# 10_USB.net
KiCad netlist of a schematic drawn in Altium Designer
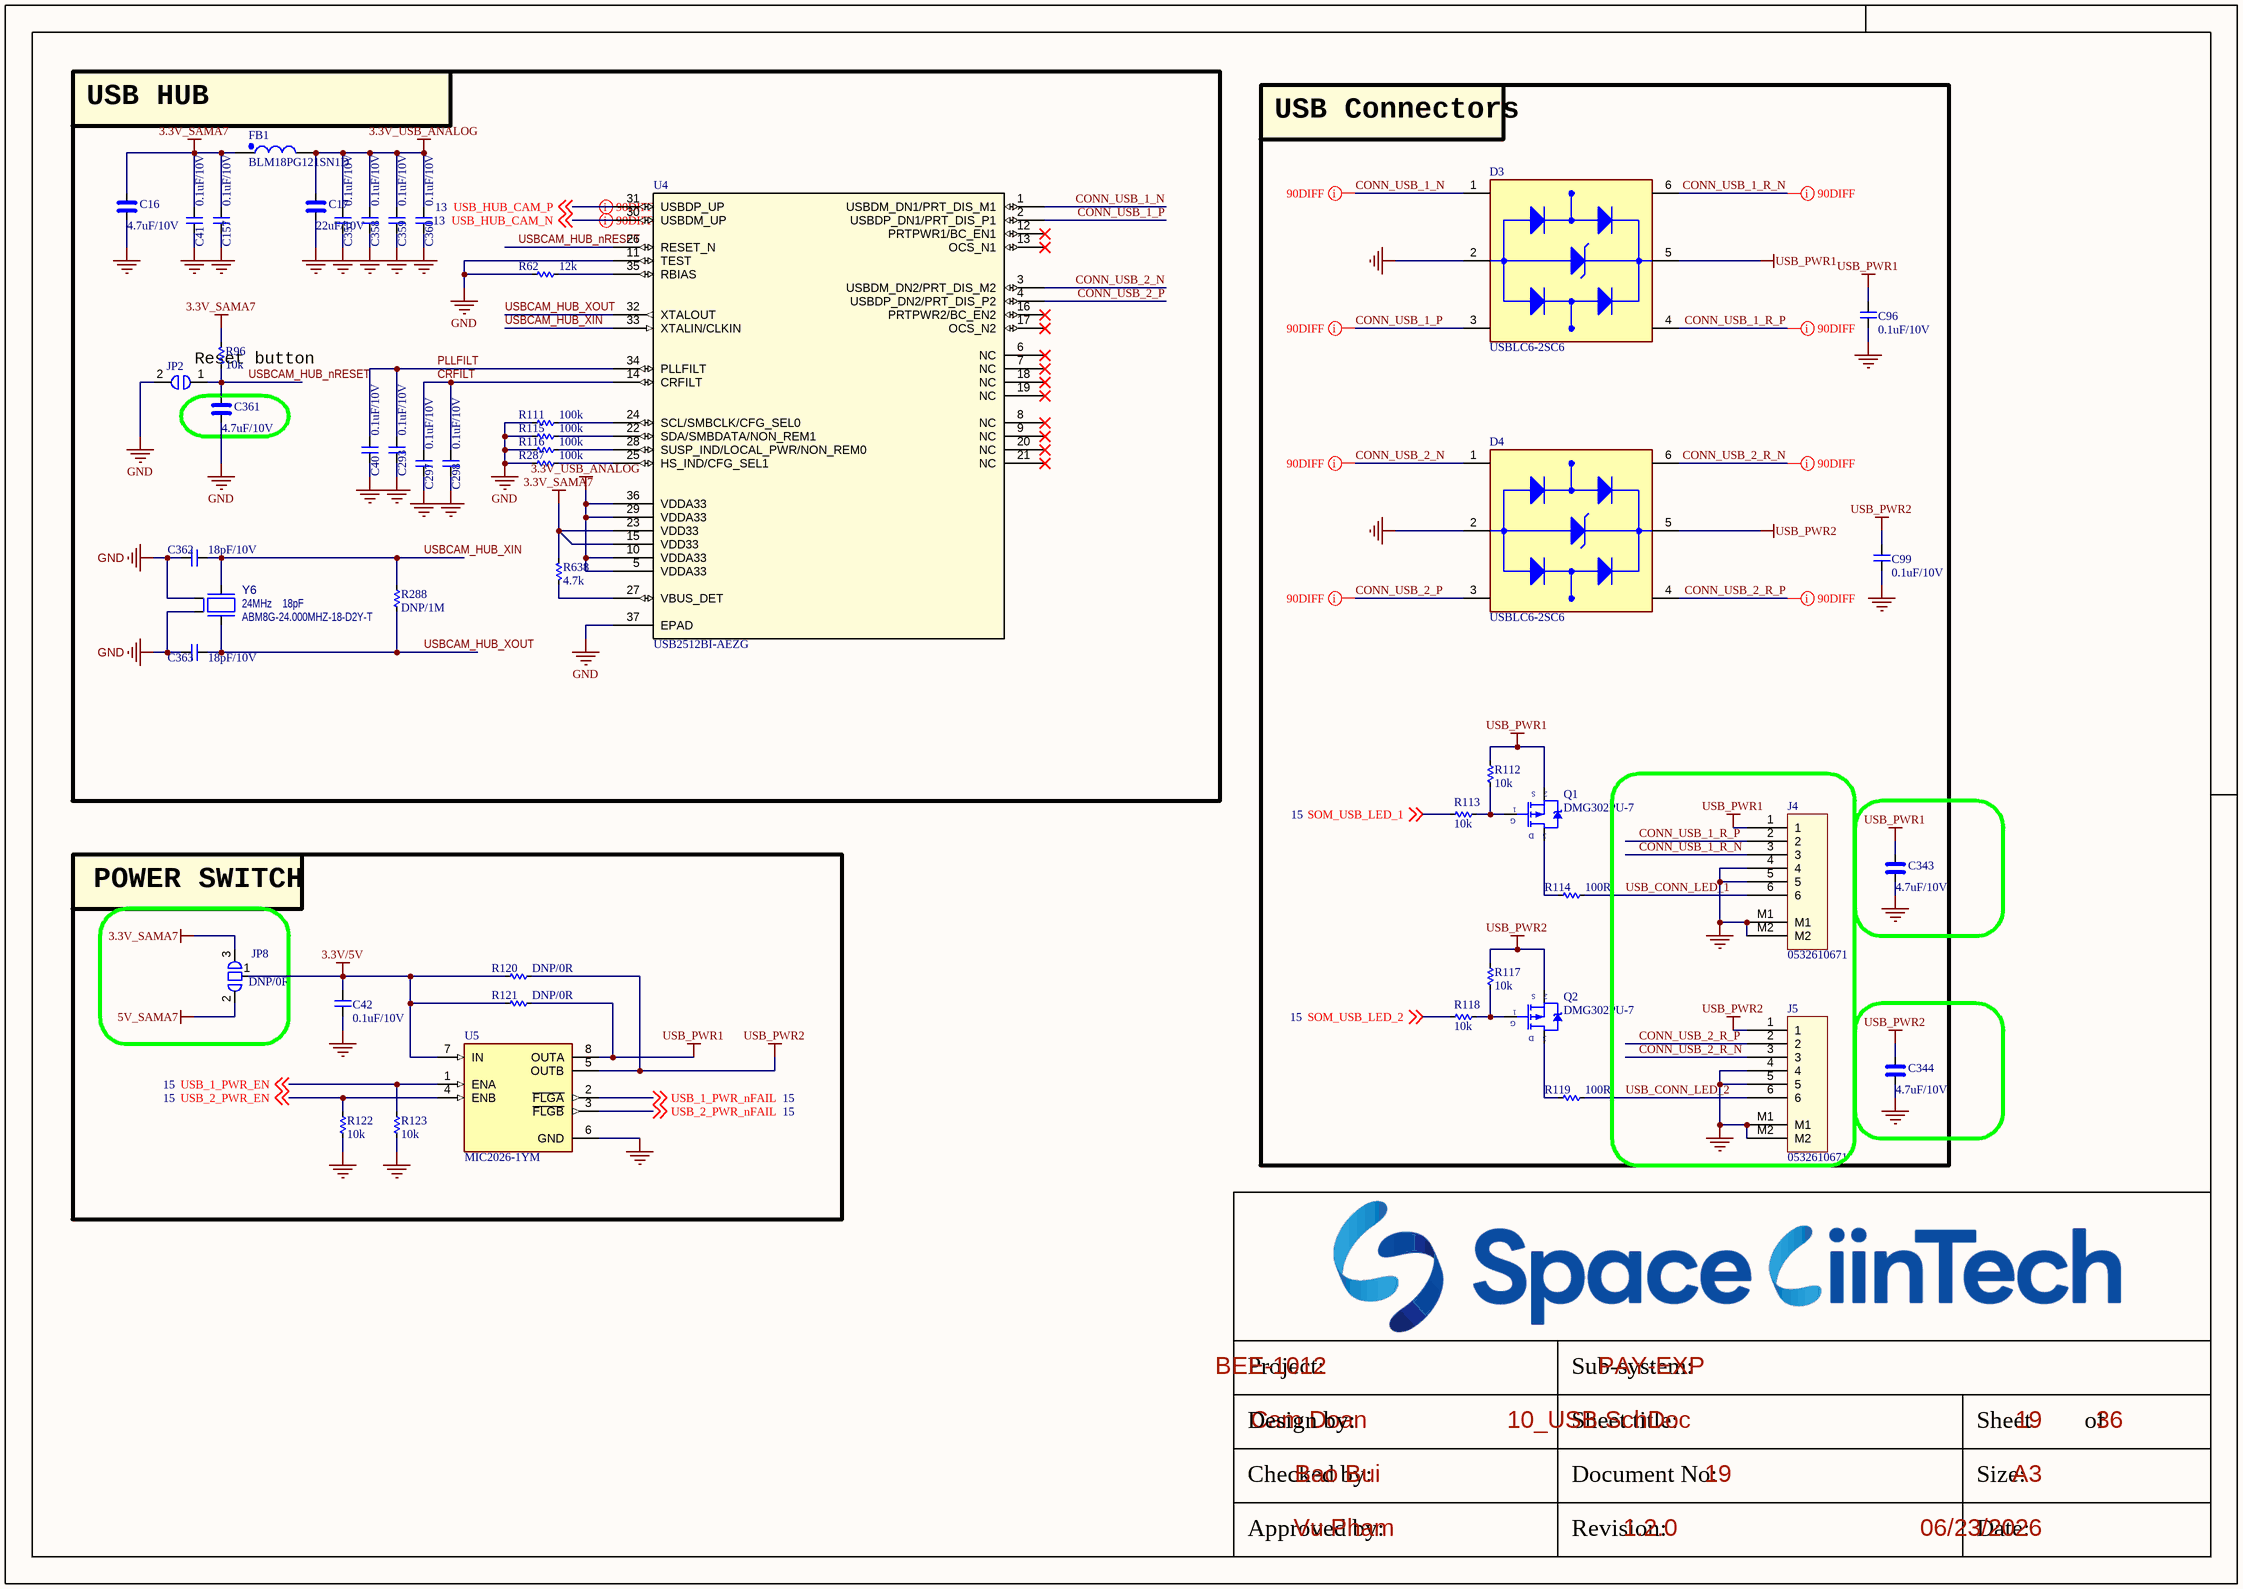
[diagram p0: 10_USB.SchDoc]

(export (version "E")
  (design (tool "Eeschema 10.0.6"))
  (components
    (comp (ref "C16")
      (value "4.7uF/10V")
      (footprint "CAP_C_1608X80")
      (description "CAP CHIP High Value")
      (libsource (lib "LABLIB") (part "_CAP_C_High_2"))
    )
    (comp (ref "C17")
      (value "22uF/10V")
      (footprint "CAP_C_1608X80")
      (description "CAP CHIP High Value")
      (libsource (lib "LABLIB") (part "_CAP_C_High_2"))
    )
    (comp (ref "C40")
      (value "0.1uF/10V")
      (footprint "CAP_C_1005X60")
      (description "CAP CHIP")
      (libsource (lib "LABLIB") (part "_CAP_C_2"))
    )
    (comp (ref "C41")
      (value "0.1uF/10V")
      (footprint "CAP_C_1005X60")
      (description "CAP CHIP")
      (libsource (lib "LABLIB") (part "_CAP_C_2"))
    )
    (comp (ref "C42")
      (value "0.1uF/10V")
      (footprint "CAP_C_1005X60")
      (description "CAP")
      (libsource (lib "LABLIB") (part "_CAP_C_2"))
    )
    (comp (ref "C96")
      (value "0.1uF/10V")
      (footprint "CAP_C_1005X60")
      (description "CAP")
      (libsource (lib "LABLIB") (part "_CAP_C_2"))
    )
    (comp (ref "C99")
      (value "0.1uF/10V")
      (footprint "CAP_C_1005X60")
      (description "CAP")
      (libsource (lib "LABLIB") (part "_CAP_C_2"))
    )
    (comp (ref "C157")
      (value "0.1uF/10V")
      (footprint "CAP_C_1005X60")
      (description "CAP CHIP")
      (libsource (lib "LABLIB") (part "_CAP_C_2"))
    )
    (comp (ref "C293")
      (value "0.1uF/10V")
      (footprint "CAP_C_1005X60")
      (description "CAP CHIP")
      (libsource (lib "LABLIB") (part "_CAP_C_2"))
    )
    (comp (ref "C297")
      (value "0.1uF/10V")
      (footprint "CAP_C_1005X60")
      (description "CAP CHIP")
      (libsource (lib "LABLIB") (part "_CAP_C_2"))
    )
    (comp (ref "C298")
      (value "0.1uF/10V")
      (footprint "CAP_C_1005X60")
      (description "CAP CHIP")
      (libsource (lib "LABLIB") (part "_CAP_C_2"))
    )
    (comp (ref "C343")
      (value "4.7uF/10V")
      (footprint "CAP_C_1608X80")
      (description "CAP CHIP High Value")
      (libsource (lib "LABLIB") (part "_CAP_C_High_2"))
    )
    (comp (ref "C344")
      (value "4.7uF/10V")
      (footprint "CAP_C_1608X80")
      (description "CAP CHIP High Value")
      (libsource (lib "LABLIB") (part "_CAP_C_High_2"))
    )
    (comp (ref "C357")
      (value "0.1uF/10V")
      (footprint "CAP_C_1005X60")
      (description "CAP CHIP")
      (libsource (lib "LABLIB") (part "_CAP_C_2"))
    )
    (comp (ref "C358")
      (value "0.1uF/10V")
      (footprint "CAP_C_1005X60")
      (description "CAP CHIP")
      (libsource (lib "LABLIB") (part "_CAP_C_2"))
    )
    (comp (ref "C359")
      (value "0.1uF/10V")
      (footprint "CAP_C_1005X60")
      (description "CAP CHIP")
      (libsource (lib "LABLIB") (part "_CAP_C_2"))
    )
    (comp (ref "C360")
      (value "0.1uF/10V")
      (footprint "CAP_C_1005X60")
      (description "CAP CHIP")
      (libsource (lib "LABLIB") (part "_CAP_C_2"))
    )
    (comp (ref "C361")
      (value "4.7uF/10V")
      (footprint "CAP_C_1608X80")
      (description "CAP CHIP High Value")
      (libsource (lib "LABLIB") (part "_CAP_C_High_2"))
    )
    (comp (ref "C362")
      (value "18pF/10V")
      (footprint "CAP_C_1005X60")
      (description "CAP CHIP")
      (libsource (lib "LABLIB") (part "_CAP_C_2"))
    )
    (comp (ref "C363")
      (value "18pF/10V")
      (footprint "CAP_C_1005X60")
      (description "CAP CHIP")
      (libsource (lib "LABLIB") (part "_CAP_C_2"))
    )
    (comp (ref "D3")
      (value "USBLC6-2SC6")
      (footprint "SOT95P280X145-6N")
      (description "17V Clamp 5A (8/20Âµs) Ipp Tvs Diode Surface Mount SOT-23-6")
      (fields (field (name "MF") "STMicroelectronics"))
      (libsource (lib "USBLC6-2SC6") (part "USBLC6-2SC6"))
    )
    (comp (ref "D4")
      (value "USBLC6-2SC6")
      (footprint "SOT95P280X145-6N")
      (description "17V Clamp 5A (8/20Âµs) Ipp Tvs Diode Surface Mount SOT-23-6")
      (fields (field (name "MF") "STMicroelectronics"))
      (libsource (lib "USBLC6-2SC6") (part "USBLC6-2SC6"))
    )
    (comp (ref "FB1")
      (value "BLM18PG121SN1D")
      (footprint "IND_C_1608X60")
      (libsource (lib "LABLIB") (part "_IND"))
    )
    (comp (ref "J4")
      (value "0532610671")
      (footprint "MOLEX_0532610671")
      (libsource (lib "LABLIB") (part "Header 6x1_2M"))
    )
    (comp (ref "J5")
      (value "0532610671")
      (footprint "MOLEX_0532610671")
      (libsource (lib "LABLIB") (part "Header 6x1_2M"))
    )
    (comp (ref "JP2")
      (value "~")
      (footprint "TESTPOINT_SHORT_120X100_60")
      (libsource (lib "LABLIB") (part "JUMPER_1_1"))
    )
    (comp (ref "JP8")
      (value "DNP/0R")
      (footprint "JUMPER_1-2_1608X60")
      (libsource (lib "LABLIB") (part "JUMPER_1_2"))
    )
    (comp (ref "Q1")
      (value "DMG302PU-7")
      (footprint "SOT95P240X120-3N")
      (libsource (lib "LABLIB") (part "MOSFET_P_GSD"))
    )
    (comp (ref "Q2")
      (value "DMG302PU-7")
      (footprint "SOT95P240X120-3N")
      (libsource (lib "LABLIB") (part "MOSFET_P_GSD"))
    )
    (comp (ref "R62")
      (value "12k")
      (footprint "RES_C_1005X40")
      (description "RES")
      (libsource (lib "LABLIB") (part "_RES_B_2"))
    )
    (comp (ref "R96")
      (value "10k")
      (footprint "RES_C_1005X40")
      (description "RES")
      (libsource (lib "LABLIB") (part "_RES_B_2"))
    )
    (comp (ref "R111")
      (value "100k")
      (footprint "RES_C_1005X40")
      (description "RES")
      (libsource (lib "LABLIB") (part "_RES_B_2"))
    )
    (comp (ref "R112")
      (value "10k")
      (footprint "RES_C_1005X40")
      (description "RES")
      (libsource (lib "LABLIB") (part "_RES_B_2"))
    )
    (comp (ref "R113")
      (value "10k")
      (footprint "RES_C_1005X40")
      (description "RES")
      (libsource (lib "LABLIB") (part "_RES_B_2"))
    )
    (comp (ref "R114")
      (value "100R")
      (footprint "RES_C_1005X40")
      (description "RES")
      (libsource (lib "LABLIB") (part "_RES_B_2"))
    )
    (comp (ref "R115")
      (value "100k")
      (footprint "RES_C_1005X40")
      (description "RES")
      (libsource (lib "LABLIB") (part "_RES_B_2"))
    )
    (comp (ref "R116")
      (value "100k")
      (footprint "RES_C_1005X40")
      (description "RES")
      (libsource (lib "LABLIB") (part "_RES_B_2"))
    )
    (comp (ref "R117")
      (value "10k")
      (footprint "RES_C_1005X40")
      (description "RES")
      (libsource (lib "LABLIB") (part "_RES_B_2"))
    )
    (comp (ref "R118")
      (value "10k")
      (footprint "RES_C_1005X40")
      (description "RES")
      (libsource (lib "LABLIB") (part "_RES_B_2"))
    )
    (comp (ref "R119")
      (value "100R")
      (footprint "RES_C_1005X40")
      (description "RES")
      (libsource (lib "LABLIB") (part "_RES_B_2"))
    )
    (comp (ref "R120")
      (value "DNP/0R")
      (footprint "RES_C_1005X40")
      (description "RES")
      (libsource (lib "LABLIB") (part "_RES_B_2"))
    )
    (comp (ref "R121")
      (value "DNP/0R")
      (footprint "RES_C_1005X40")
      (description "RES")
      (libsource (lib "LABLIB") (part "_RES_B_2"))
    )
    (comp (ref "R122")
      (value "10k")
      (footprint "RES_C_1005X40")
      (description "RES")
      (libsource (lib "LABLIB") (part "_RES_B_2"))
    )
    (comp (ref "R123")
      (value "10k")
      (footprint "RES_C_1005X40")
      (description "RES")
      (libsource (lib "LABLIB") (part "_RES_B_2"))
    )
    (comp (ref "R287")
      (value "100k")
      (footprint "RES_C_1005X40")
      (description "RES")
      (libsource (lib "LABLIB") (part "_RES_B_2"))
    )
    (comp (ref "R288")
      (value "DNP/1M")
      (footprint "RES_C_1005X40")
      (description "RES")
      (libsource (lib "LABLIB") (part "_RES_B_2"))
    )
    (comp (ref "R638")
      (value "4.7k")
      (footprint "RES_C_1005X40")
      (description "RES")
      (libsource (lib "LABLIB") (part "_RES_B_2"))
    )
    (comp (ref "U4")
      (value "USB2512BI-AEZG")
      (footprint "QFN36_6X6MC_MCH")
      (description "Description")
      (fields (field (name "COPYRIGHT") "Copyright (C) 2026 Ultra Librarian. All rights reserved."))
      (libsource (lib "LABLIB") (part "IC_USB_HUB_USB2512BI-AEZG"))
    )
    (comp (ref "U5")
      (value "MIC2026-1YM")
      (footprint "SOIC127P602X173-8N")
      (description "Power Switch/Driver 1:2 N-Channel 1.25A 8-SOIC")
      (fields (field (name "MF") "Microchip"))
      (libsource (lib "LABLIB") (part "IC_PWRSW_MIC2026-1YM"))
    )
    (comp (ref "Y6")
      (value "24MHz")
      (footprint "CRYSTAL_ABM8G")
      (description "Crystal")
      (fields
        (field (name "LOAD CAPACITANCE") "18pF")
        (field (name "MANUFACTURER PART NUMBER 1") "ABM8G-24.000MHZ-18-D2Y-T")
        (field (name "Comment") "Crystal 4 Pins")
        (field (name "OWNER") "Mark Loper")
      )
      (libsource (lib "MCHP-CDB") (part "Crystal 4 Pins"))
    )
  )
  (nets
    (net (code "1") (name "/CONN_USB_1_N") (class "Default")
      (node (ref "D3") (pin "1") (pinfunction "I/O1_IN_1") (pintype "passive"))
      (node (ref "U4") (pin "1") (pinfunction "USBDM_DN1/PRT_DIS_M1_1") (pintype "bidirectional"))
    )
    (net (code "2") (name "/CONN_USB_1_P") (class "Default")
      (node (ref "D3") (pin "3") (pinfunction "I/O2_IN_3") (pintype "passive"))
      (node (ref "U4") (pin "2") (pinfunction "USBDP_DN1/PRT_DIS_P1_2") (pintype "bidirectional"))
    )
    (net (code "3") (name "/CONN_USB_1_R_N") (class "Default")
      (node (ref "D3") (pin "6") (pinfunction "I/O1_OUT_6") (pintype "passive"))
      (node (ref "J4") (pin "3") (pinfunction "3_3") (pintype "passive"))
    )
    (net (code "4") (name "/CONN_USB_1_R_P") (class "Default")
      (node (ref "D3") (pin "4") (pinfunction "I/O2_OUT_4") (pintype "passive"))
      (node (ref "J4") (pin "2") (pinfunction "2_2") (pintype "passive"))
    )
    (net (code "5") (name "/CONN_USB_2_N") (class "Default")
      (node (ref "D4") (pin "1") (pinfunction "I/O1_IN_1") (pintype "passive"))
      (node (ref "U4") (pin "3") (pinfunction "USBDM_DN2/PRT_DIS_M2_3") (pintype "bidirectional"))
    )
    (net (code "6") (name "/CONN_USB_2_P") (class "Default")
      (node (ref "D4") (pin "3") (pinfunction "I/O2_IN_3") (pintype "passive"))
      (node (ref "U4") (pin "4") (pinfunction "USBDP_DN2/PRT_DIS_P2_4") (pintype "bidirectional"))
    )
    (net (code "7") (name "/CONN_USB_2_R_N") (class "Default")
      (node (ref "D4") (pin "6") (pinfunction "I/O1_OUT_6") (pintype "passive"))
      (node (ref "J5") (pin "3") (pinfunction "3_3") (pintype "passive"))
    )
    (net (code "8") (name "/CONN_USB_2_R_P") (class "Default")
      (node (ref "D4") (pin "4") (pinfunction "I/O2_OUT_4") (pintype "passive"))
      (node (ref "J5") (pin "2") (pinfunction "2_2") (pintype "passive"))
    )
    (net (code "9") (name "/CRFILT") (class "Default")
      (node (ref "C297") (pin "2") (pinfunction "2_2") (pintype "passive"))
      (node (ref "C298") (pin "2") (pinfunction "2_2") (pintype "passive"))
      (node (ref "U4") (pin "14") (pinfunction "CRFILT_14") (pintype "bidirectional"))
    )
    (net (code "10") (name "/PLLFILT") (class "Default")
      (node (ref "C293") (pin "2") (pinfunction "2_2") (pintype "passive"))
      (node (ref "C40") (pin "2") (pinfunction "2_2") (pintype "passive"))
      (node (ref "U4") (pin "34") (pinfunction "PLLFILT_34") (pintype "bidirectional"))
    )
    (net (code "11") (name "/USBCAM_HUB_XIN") (class "Default")
      (node (ref "C362") (pin "1") (pinfunction "1_1") (pintype "passive"))
      (node (ref "R288") (pin "1") (pinfunction "1_1") (pintype "passive"))
      (node (ref "U4") (pin "33") (pinfunction "XTALIN/CLKIN_33") (pintype "input"))
      (node (ref "Y6") (pin "3") (pinfunction "Osc2_3") (pintype "passive"))
    )
    (net (code "12") (name "/USBCAM_HUB_XOUT") (class "Default")
      (node (ref "C363") (pin "1") (pinfunction "1_1") (pintype "passive"))
      (node (ref "R288") (pin "2") (pinfunction "2_2") (pintype "passive"))
      (node (ref "U4") (pin "32") (pinfunction "XTALOUT_32") (pintype "output"))
      (node (ref "Y6") (pin "1") (pinfunction "Osc1_1") (pintype "passive"))
    )
    (net (code "13") (name "/USBCAM_HUB_nRESET") (class "Default")
      (node (ref "C361") (pin "1") (pinfunction "1_1") (pintype "passive"))
      (node (ref "JP2") (pin "1") (pinfunction "1_1") (pintype "passive"))
      (node (ref "R96") (pin "2") (pinfunction "2_2") (pintype "passive"))
      (node (ref "U4") (pin "26") (pinfunction "RESET_N_26") (pintype "bidirectional"))
    )
    (net (code "14") (name "/USB_CONN_LED_1") (class "Default")
      (node (ref "J4") (pin "6") (pinfunction "6_6") (pintype "passive"))
      (node (ref "R114") (pin "2") (pinfunction "2_2") (pintype "passive"))
    )
    (net (code "15") (name "/USB_CONN_LED_2") (class "Default")
      (node (ref "J5") (pin "6") (pinfunction "6_6") (pintype "passive"))
      (node (ref "R119") (pin "2") (pinfunction "2_2") (pintype "passive"))
    )
    (net (code "16") (name "3.3V_SAMA7") (class "Default")
      (node (ref "C157") (pin "2") (pinfunction "2_2") (pintype "passive"))
      (node (ref "C16") (pin "1") (pinfunction "1_1") (pintype "passive"))
      (node (ref "C41") (pin "2") (pinfunction "2_2") (pintype "passive"))
      (node (ref "FB1") (pin "1") (pinfunction "1_1") (pintype "passive"))
      (node (ref "JP8") (pin "3") (pinfunction "3_3") (pintype "passive"))
      (node (ref "R638") (pin "1") (pinfunction "1_1") (pintype "passive"))
      (node (ref "R96") (pin "1") (pinfunction "1_1") (pintype "passive"))
      (node (ref "U4") (pin "15") (pinfunction "VDD33_15") (pintype "power_in"))
      (node (ref "U4") (pin "23") (pinfunction "VDD33_23") (pintype "power_in"))
    )
    (net (code "17") (name "3.3V_USB_ANALOG") (class "Default")
      (node (ref "C17") (pin "1") (pinfunction "1_1") (pintype "passive"))
      (node (ref "C357") (pin "2") (pinfunction "2_2") (pintype "passive"))
      (node (ref "C358") (pin "2") (pinfunction "2_2") (pintype "passive"))
      (node (ref "C359") (pin "2") (pinfunction "2_2") (pintype "passive"))
      (node (ref "C360") (pin "2") (pinfunction "2_2") (pintype "passive"))
      (node (ref "FB1") (pin "2") (pinfunction "2_2") (pintype "passive"))
      (node (ref "U4") (pin "10") (pinfunction "VDDA33_10") (pintype "power_in"))
      (node (ref "U4") (pin "29") (pinfunction "VDDA33_29") (pintype "power_in"))
      (node (ref "U4") (pin "36") (pinfunction "VDDA33_36") (pintype "power_in"))
      (node (ref "U4") (pin "5") (pinfunction "VDDA33_5") (pintype "power_in"))
    )
    (net (code "18") (name "3.3V{slash}5V") (class "Default")
      (node (ref "C42") (pin "2") (pinfunction "2_2") (pintype "passive"))
      (node (ref "JP8") (pin "1") (pinfunction "1_1") (pintype "passive"))
      (node (ref "R120") (pin "2") (pinfunction "2_2") (pintype "passive"))
      (node (ref "R121") (pin "2") (pinfunction "2_2") (pintype "passive"))
      (node (ref "U5") (pin "7") (pinfunction "IN_7") (pintype "input"))
    )
    (net (code "19") (name "5V_SAMA7") (class "Default")
      (node (ref "JP8") (pin "2") (pinfunction "2_2") (pintype "passive"))
    )
    (net (code "20") (name "GND") (class "Default")
      (node (ref "C157") (pin "1") (pinfunction "1_1") (pintype "passive"))
      (node (ref "C16") (pin "2") (pinfunction "2_2") (pintype "passive"))
      (node (ref "C17") (pin "2") (pinfunction "2_2") (pintype "passive"))
      (node (ref "C293") (pin "1") (pinfunction "1_1") (pintype "passive"))
      (node (ref "C297") (pin "1") (pinfunction "1_1") (pintype "passive"))
      (node (ref "C298") (pin "1") (pinfunction "1_1") (pintype "passive"))
      (node (ref "C343") (pin "2") (pinfunction "2_2") (pintype "passive"))
      (node (ref "C344") (pin "2") (pinfunction "2_2") (pintype "passive"))
      (node (ref "C357") (pin "1") (pinfunction "1_1") (pintype "passive"))
      (node (ref "C358") (pin "1") (pinfunction "1_1") (pintype "passive"))
      (node (ref "C359") (pin "1") (pinfunction "1_1") (pintype "passive"))
      (node (ref "C360") (pin "1") (pinfunction "1_1") (pintype "passive"))
      (node (ref "C361") (pin "2") (pinfunction "2_2") (pintype "passive"))
      (node (ref "C362") (pin "2") (pinfunction "2_2") (pintype "passive"))
      (node (ref "C363") (pin "2") (pinfunction "2_2") (pintype "passive"))
      (node (ref "C40") (pin "1") (pinfunction "1_1") (pintype "passive"))
      (node (ref "C41") (pin "1") (pinfunction "1_1") (pintype "passive"))
      (node (ref "C42") (pin "1") (pinfunction "1_1") (pintype "passive"))
      (node (ref "C96") (pin "1") (pinfunction "1_1") (pintype "passive"))
      (node (ref "C99") (pin "1") (pinfunction "1_1") (pintype "passive"))
      (node (ref "D3") (pin "2") (pinfunction "GND_2") (pintype "power_in"))
      (node (ref "D4") (pin "2") (pinfunction "GND_2") (pintype "power_in"))
      (node (ref "J4") (pin "4") (pinfunction "4_4") (pintype "passive"))
      (node (ref "J4") (pin "5") (pinfunction "5_5") (pintype "passive"))
      (node (ref "J4") (pin "M1") (pinfunction "M1_M1") (pintype "passive"))
      (node (ref "J4") (pin "M2") (pinfunction "M2_M2") (pintype "passive"))
      (node (ref "J5") (pin "4") (pinfunction "4_4") (pintype "passive"))
      (node (ref "J5") (pin "5") (pinfunction "5_5") (pintype "passive"))
      (node (ref "J5") (pin "M1") (pinfunction "M1_M1") (pintype "passive"))
      (node (ref "J5") (pin "M2") (pinfunction "M2_M2") (pintype "passive"))
      (node (ref "JP2") (pin "2") (pinfunction "2_2") (pintype "passive"))
      (node (ref "R111") (pin "1") (pinfunction "1_1") (pintype "passive"))
      (node (ref "R115") (pin "1") (pinfunction "1_1") (pintype "passive"))
      (node (ref "R116") (pin "1") (pinfunction "1_1") (pintype "passive"))
      (node (ref "R122") (pin "2") (pinfunction "2_2") (pintype "passive"))
      (node (ref "R123") (pin "2") (pinfunction "2_2") (pintype "passive"))
      (node (ref "R287") (pin "1") (pinfunction "1_1") (pintype "passive"))
      (node (ref "R62") (pin "1") (pinfunction "1_1") (pintype "passive"))
      (node (ref "U4") (pin "11") (pinfunction "TEST_11") (pintype "bidirectional"))
      (node (ref "U4") (pin "37") (pinfunction "EPAD_37") (pintype "passive"))
      (node (ref "U5") (pin "6") (pinfunction "GND_6") (pintype "power_in"))
      (node (ref "Y6") (pin "2") (pinfunction "GND_2") (pintype "power_in"))
      (node (ref "Y6") (pin "4") (pinfunction "GND_4") (pintype "power_in"))
    )
    (net (code "21") (name "Net-(Q1-D)") (class "Default")
      (node (ref "Q1") (pin "3") (pinfunction "D_3") (pintype "passive"))
      (node (ref "R114") (pin "1") (pinfunction "1_1") (pintype "passive"))
    )
    (net (code "22") (name "Net-(Q1-G)") (class "Default")
      (node (ref "Q1") (pin "1") (pinfunction "G_1") (pintype "passive"))
      (node (ref "R112") (pin "2") (pinfunction "2_2") (pintype "passive"))
      (node (ref "R113") (pin "2") (pinfunction "2_2") (pintype "passive"))
    )
    (net (code "23") (name "Net-(Q2-D)") (class "Default")
      (node (ref "Q2") (pin "3") (pinfunction "D_3") (pintype "passive"))
      (node (ref "R119") (pin "1") (pinfunction "1_1") (pintype "passive"))
    )
    (net (code "24") (name "Net-(Q2-G)") (class "Default")
      (node (ref "Q2") (pin "1") (pinfunction "G_1") (pintype "passive"))
      (node (ref "R117") (pin "2") (pinfunction "2_2") (pintype "passive"))
      (node (ref "R118") (pin "2") (pinfunction "2_2") (pintype "passive"))
    )
    (net (code "25") (name "Net-(U4-HS_IND{slash}CFG_SEL1)") (class "Default")
      (node (ref "R287") (pin "2") (pinfunction "2_2") (pintype "passive"))
      (node (ref "U4") (pin "25") (pinfunction "HS_IND/CFG_SEL1_25") (pintype "bidirectional"))
    )
    (net (code "26") (name "Net-(U4-RBIAS)") (class "Default")
      (node (ref "R62") (pin "2") (pinfunction "2_2") (pintype "passive"))
      (node (ref "U4") (pin "35") (pinfunction "RBIAS_35") (pintype "bidirectional"))
    )
    (net (code "27") (name "Net-(U4-SCL{slash}SMBCLK{slash}CFG_SEL0)") (class "Default")
      (node (ref "R111") (pin "2") (pinfunction "2_2") (pintype "passive"))
      (node (ref "U4") (pin "24") (pinfunction "SCL/SMBCLK/CFG_SEL0_24") (pintype "bidirectional"))
    )
    (net (code "28") (name "Net-(U4-SDA{slash}SMBDATA{slash}NON_REM1)") (class "Default")
      (node (ref "R115") (pin "2") (pinfunction "2_2") (pintype "passive"))
      (node (ref "U4") (pin "22") (pinfunction "SDA/SMBDATA/NON_REM1_22") (pintype "bidirectional"))
    )
    (net (code "29") (name "Net-(U4-SUSP_IND{slash}LOCAL_PWR{slash}NON_REM0)") (class "Default")
      (node (ref "R116") (pin "2") (pinfunction "2_2") (pintype "passive"))
      (node (ref "U4") (pin "28") (pinfunction "SUSP_IND/LOCAL_PWR/NON_REM0_28") (pintype "bidirectional"))
    )
    (net (code "30") (name "Net-(U4-VBUS_DET)") (class "Default")
      (node (ref "R638") (pin "2") (pinfunction "2_2") (pintype "passive"))
      (node (ref "U4") (pin "27") (pinfunction "VBUS_DET_27") (pintype "bidirectional"))
    )
    (net (code "31") (name "SOM_USB_LED_1") (class "Default")
      (node (ref "R113") (pin "1") (pinfunction "1_1") (pintype "passive"))
    )
    (net (code "32") (name "SOM_USB_LED_2") (class "Default")
      (node (ref "R118") (pin "1") (pinfunction "1_1") (pintype "passive"))
    )
    (net (code "33") (name "USB_1_PWR_EN") (class "Default")
      (node (ref "R123") (pin "1") (pinfunction "1_1") (pintype "passive"))
      (node (ref "U5") (pin "1") (pinfunction "ENA_1") (pintype "input"))
    )
    (net (code "34") (name "USB_1_PWR_nFAIL") (class "Default")
      (node (ref "U5") (pin "2") (pinfunction "~{FLGA}_2") (pintype "output"))
    )
    (net (code "35") (name "USB_2_PWR_EN") (class "Default")
      (node (ref "R122") (pin "1") (pinfunction "1_1") (pintype "passive"))
      (node (ref "U5") (pin "4") (pinfunction "ENB_4") (pintype "input"))
    )
    (net (code "36") (name "USB_2_PWR_nFAIL") (class "Default")
      (node (ref "U5") (pin "3") (pinfunction "~{FLGB}_3") (pintype "output"))
    )
    (net (code "37") (name "USB_HUB_CAM_N") (class "Default")
      (node (ref "U4") (pin "30") (pinfunction "USBDM_UP_30") (pintype "bidirectional"))
    )
    (net (code "38") (name "USB_HUB_CAM_P") (class "Default")
      (node (ref "U4") (pin "31") (pinfunction "USBDP_UP_31") (pintype "bidirectional"))
    )
    (net (code "39") (name "USB_PWR1") (class "Default")
      (node (ref "C343") (pin "1") (pinfunction "1_1") (pintype "passive"))
      (node (ref "C96") (pin "2") (pinfunction "2_2") (pintype "passive"))
      (node (ref "D3") (pin "5") (pinfunction "VBUS_5") (pintype "power_in"))
      (node (ref "J4") (pin "1") (pinfunction "1_1") (pintype "passive"))
      (node (ref "Q1") (pin "2") (pinfunction "S_2") (pintype "passive"))
      (node (ref "R112") (pin "1") (pinfunction "1_1") (pintype "passive"))
      (node (ref "R121") (pin "1") (pinfunction "1_1") (pintype "passive"))
      (node (ref "U5") (pin "8") (pinfunction "OUTA_8") (pintype "passive"))
    )
    (net (code "40") (name "USB_PWR2") (class "Default")
      (node (ref "C344") (pin "1") (pinfunction "1_1") (pintype "passive"))
      (node (ref "C99") (pin "2") (pinfunction "2_2") (pintype "passive"))
      (node (ref "D4") (pin "5") (pinfunction "VBUS_5") (pintype "power_in"))
      (node (ref "J5") (pin "1") (pinfunction "1_1") (pintype "passive"))
      (node (ref "Q2") (pin "2") (pinfunction "S_2") (pintype "passive"))
      (node (ref "R117") (pin "1") (pinfunction "1_1") (pintype "passive"))
      (node (ref "R120") (pin "1") (pinfunction "1_1") (pintype "passive"))
      (node (ref "U5") (pin "5") (pinfunction "OUTB_5") (pintype "passive"))
    )
    (net (code "41") (name "unconnected-(U4-NC-Pad6)") (class "Default")
      (node (ref "U4") (pin "6") (pinfunction "NC_6") (pintype "passive+no_connect"))
    )
    (net (code "42") (name "unconnected-(U4-NC-Pad7)") (class "Default")
      (node (ref "U4") (pin "7") (pinfunction "NC_7") (pintype "passive+no_connect"))
    )
    (net (code "43") (name "unconnected-(U4-NC-Pad8)") (class "Default")
      (node (ref "U4") (pin "8") (pinfunction "NC_8") (pintype "passive+no_connect"))
    )
    (net (code "44") (name "unconnected-(U4-NC-Pad9)") (class "Default")
      (node (ref "U4") (pin "9") (pinfunction "NC_9") (pintype "passive+no_connect"))
    )
    (net (code "45") (name "unconnected-(U4-NC-Pad18)") (class "Default")
      (node (ref "U4") (pin "18") (pinfunction "NC_18") (pintype "passive+no_connect"))
    )
    (net (code "46") (name "unconnected-(U4-NC-Pad19)") (class "Default")
      (node (ref "U4") (pin "19") (pinfunction "NC_19") (pintype "passive+no_connect"))
    )
    (net (code "47") (name "unconnected-(U4-NC-Pad20)") (class "Default")
      (node (ref "U4") (pin "20") (pinfunction "NC_20") (pintype "passive+no_connect"))
    )
    (net (code "48") (name "unconnected-(U4-NC-Pad21)") (class "Default")
      (node (ref "U4") (pin "21") (pinfunction "NC_21") (pintype "passive+no_connect"))
    )
    (net (code "49") (name "unconnected-(U4-OCS_N1-Pad13)") (class "Default")
      (node (ref "U4") (pin "13") (pinfunction "OCS_N1_13") (pintype "bidirectional+no_connect"))
    )
    (net (code "50") (name "unconnected-(U4-OCS_N2-Pad17)") (class "Default")
      (node (ref "U4") (pin "17") (pinfunction "OCS_N2_17") (pintype "bidirectional+no_connect"))
    )
    (net (code "51") (name "unconnected-(U4-PRTPWR1{slash}BC_EN1-Pad12)") (class "Default")
      (node (ref "U4") (pin "12") (pinfunction "PRTPWR1/BC_EN1_12") (pintype "bidirectional+no_connect"))
    )
    (net (code "52") (name "unconnected-(U4-PRTPWR2{slash}BC_EN2-Pad16)") (class "Default")
      (node (ref "U4") (pin "16") (pinfunction "PRTPWR2/BC_EN2_16") (pintype "bidirectional+no_connect"))
    )
  )
)
